# Grownetics_Humidity_and_Temperature_Sens.net
KiCad netlist of a schematic drawn in EAGLE
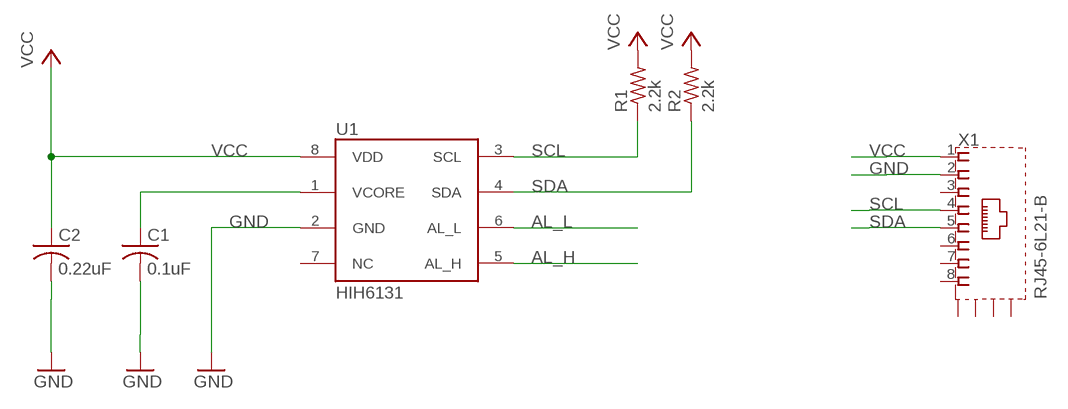
[diagram p0: schematic, sheet 1]

(export (version "E")
  (design (tool "Eeschema 10.0.6"))
  (components
    (comp (ref "C1")
      (value "0.1uF")
      (footprint "eagle-import:C0805")
      (fields (field (name "MPN") "C0805S104K5RACAUTO"))
      (libsource (lib "eagle-import") (part "C-USC0805"))
    )
    (comp (ref "C2")
      (value "0.22uF")
      (footprint "eagle-import:C0805")
      (fields (field (name "MPN") "C0805X224K5RACTU"))
      (libsource (lib "eagle-import") (part "C-USC0805"))
    )
    (comp (ref "R1")
      (value "2.2k")
      (footprint "eagle-import:R0805")
      (fields (field (name "MPN") "SR1-0805-222"))
      (libsource (lib "eagle-import") (part "R-US_R0805"))
    )
    (comp (ref "R2")
      (value "2.2k")
      (footprint "eagle-import:R0805")
      (fields (field (name "MPN") "SR1-0805-222"))
      (libsource (lib "eagle-import") (part "R-US_R0805"))
    )
    (comp (ref "U1")
      (value "HIH6131")
      (footprint "eagle-import:SOIC8")
      (fields (field (name "MPN") "HIH6131-021-001"))
      (libsource (lib "eagle-import") (part "HIH6131"))
    )
    (comp (ref "X1")
      (value "RJ45-6L21-B")
      (footprint "eagle-import:RJ45-SHIELD1")
      (fields (field (name "MPN") "RJE71-188-1401") (field (name "OC_NEWARK") "47W2082"))
      (libsource (lib "eagle-import") (part "RJ4521-B-6L"))
    )
  )
  (nets
    (net (code "1") (name "/AL_H") (class "Default")
      (node (ref "U1") (pin "5") (pinfunction "AL_H_5") (pintype "bidirectional"))
    )
    (net (code "2") (name "/AL_L") (class "Default")
      (node (ref "U1") (pin "6") (pinfunction "AL_L_6") (pintype "bidirectional"))
    )
    (net (code "3") (name "/SCL") (class "Default")
      (node (ref "R1") (pin "1") (pinfunction "1_1") (pintype "passive"))
      (node (ref "U1") (pin "3") (pinfunction "SCL_3") (pintype "bidirectional"))
      (node (ref "X1") (pin "4") (pinfunction "4_4") (pintype "passive"))
    )
    (net (code "4") (name "/SDA") (class "Default")
      (node (ref "R2") (pin "1") (pinfunction "1_1") (pintype "passive"))
      (node (ref "U1") (pin "4") (pinfunction "SDA_4") (pintype "bidirectional"))
      (node (ref "X1") (pin "5") (pinfunction "5_5") (pintype "passive"))
    )
    (net (code "5") (name "GND") (class "Default")
      (node (ref "C1") (pin "2") (pinfunction "2_2") (pintype "passive"))
      (node (ref "C2") (pin "2") (pinfunction "2_2") (pintype "passive"))
      (node (ref "U1") (pin "2") (pinfunction "GND_2") (pintype "bidirectional"))
      (node (ref "X1") (pin "2") (pinfunction "2_2") (pintype "passive"))
    )
    (net (code "6") (name "Net-(U1-VCORE)") (class "Default")
      (node (ref "C1") (pin "1") (pinfunction "1_1") (pintype "passive"))
      (node (ref "U1") (pin "1") (pinfunction "VCORE_1") (pintype "bidirectional"))
    )
    (net (code "7") (name "VCC") (class "Default")
      (node (ref "C2") (pin "1") (pinfunction "1_1") (pintype "passive"))
      (node (ref "R1") (pin "2") (pinfunction "2_2") (pintype "passive"))
      (node (ref "R2") (pin "2") (pinfunction "2_2") (pintype "passive"))
      (node (ref "U1") (pin "8") (pinfunction "VDD_8") (pintype "bidirectional"))
      (node (ref "X1") (pin "1") (pinfunction "1_1") (pintype "passive"))
    )
    (net (code "8") (name "unconnected-(U1-NC-Pad7)") (class "Default")
      (node (ref "U1") (pin "7") (pinfunction "NC_7") (pintype "bidirectional"))
    )
    (net (code "9") (name "unconnected-(X1-Pad3)") (class "Default")
      (node (ref "X1") (pin "3") (pinfunction "3_3") (pintype "passive"))
    )
    (net (code "10") (name "unconnected-(X1-Pad6)") (class "Default")
      (node (ref "X1") (pin "6") (pinfunction "6_6") (pintype "passive"))
    )
    (net (code "11") (name "unconnected-(X1-Pad7)") (class "Default")
      (node (ref "X1") (pin "7") (pinfunction "7_7") (pintype "passive"))
    )
    (net (code "12") (name "unconnected-(X1-Pad8)") (class "Default")
      (node (ref "X1") (pin "8") (pinfunction "8_8") (pintype "passive"))
    )
    (net (code "13") (name "unconnected-(X1-S-PadS1)") (class "Default")
      (node (ref "X1") (pin "S1") (pinfunction "S_S1") (pintype "passive"))
    )
    (net (code "14") (name "unconnected-(X1-S-PadS2)") (class "Default")
      (node (ref "X1") (pin "S2") (pinfunction "S_S2") (pintype "passive"))
    )
    (net (code "15") (name "unconnected-(X1-S-PadS3)") (class "Default")
      (node (ref "X1") (pin "S3") (pinfunction "S_S3") (pintype "passive"))
    )
    (net (code "16") (name "unconnected-(X1-S-PadS4)") (class "Default")
      (node (ref "X1") (pin "S4") (pinfunction "S_S4") (pintype "passive"))
    )
  )
)
